# Balancer.net
KiCad netlist of a schematic drawn in Altium Designer
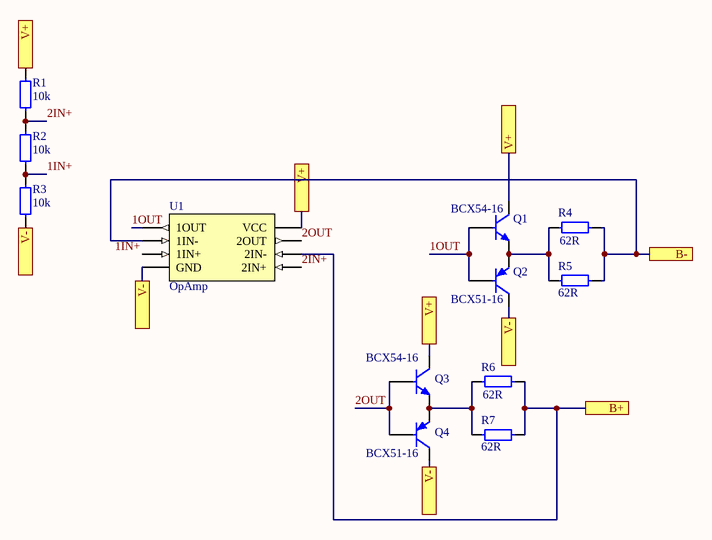
[diagram p0: Balancer.SchDoc]

(export (version "E")
  (design (tool "Eeschema 10.0.6"))
  (components
    (comp (ref "Q1")
      (value "BCX54-16")
      (footprint "SOT-89")
      (description "NPN general-purpose transistors")
      (fields (field (name "PART NUMBER") "BC817-40,215") (field (name "MANUFACTURER") "Nexperia"))
      (libsource (lib "BRT_Components") (part "NPN [BC817]"))
    )
    (comp (ref "Q2")
      (value "BCX51-16")
      (footprint "SOT-89")
      (description "PNP general-purpose transistors")
      (fields (field (name "PART NUMBER") "BC807,215") (field (name "MANUFACTURER") "Nexperia"))
      (libsource (lib "BRT_Components") (part "PNP [BC807]"))
    )
    (comp (ref "Q3")
      (value "BCX54-16")
      (footprint "SOT-89")
      (description "NPN general-purpose transistors")
      (fields (field (name "PART NUMBER") "BC817-40,215") (field (name "MANUFACTURER") "Nexperia"))
      (libsource (lib "BRT_Components") (part "NPN [BC817]"))
    )
    (comp (ref "Q4")
      (value "BCX51-16")
      (footprint "SOT-89")
      (description "PNP general-purpose transistors")
      (fields (field (name "PART NUMBER") "BC807,215") (field (name "MANUFACTURER") "Nexperia"))
      (libsource (lib "BRT_Components") (part "PNP [BC807]"))
    )
    (comp (ref "R1")
      (value "10k")
      (footprint "0805 Resistor")
      (description "0.125W 0805 10k, 1%")
      (fields (field (name "PART NUMBER") "RC0805FR-0710KL") (field (name "MANUFACTURER") "Taiwan"))
      (libsource (lib "BRT_Components") (part "Res 10k (0805)"))
    )
    (comp (ref "R2")
      (value "10k")
      (footprint "0805 Resistor")
      (description "0.125W 0805 10k, 1%")
      (fields (field (name "PART NUMBER") "RC0805FR-0710KL") (field (name "MANUFACTURER") "Taiwan"))
      (libsource (lib "BRT_Components") (part "Res 10k (0805)"))
    )
    (comp (ref "R3")
      (value "10k")
      (footprint "0805 Resistor")
      (description "0.125W 0805 10k, 1%")
      (fields (field (name "PART NUMBER") "RC0805FR-0710KL") (field (name "MANUFACTURER") "Taiwan"))
      (libsource (lib "BRT_Components") (part "Res 10k (0805)"))
    )
    (comp (ref "R4")
      (value "62R")
      (footprint "2512 Resistor")
      (description "1W 2512 62R, 1%")
      (fields (field (name "PART NUMBER") "RC2512FR-0762RL") (field (name "MANUFACTURER") "Taiwan"))
      (libsource (lib "BRT_Components") (part "Res 62R (2512)"))
    )
    (comp (ref "R5")
      (value "62R")
      (footprint "2512 Resistor")
      (description "1W 2512 62R, 1%")
      (fields (field (name "PART NUMBER") "RC2512FR-0762RL") (field (name "MANUFACTURER") "Taiwan"))
      (libsource (lib "BRT_Components") (part "Res 62R (2512)"))
    )
    (comp (ref "R6")
      (value "62R")
      (footprint "2512 Resistor")
      (description "1W 2512 62R, 1%")
      (fields (field (name "PART NUMBER") "RC2512FR-0762RL") (field (name "MANUFACTURER") "Taiwan"))
      (libsource (lib "BRT_Components") (part "Res 62R (2512)"))
    )
    (comp (ref "R7")
      (value "62R")
      (footprint "2512 Resistor")
      (description "1W 2512 62R, 1%")
      (fields (field (name "PART NUMBER") "RC2512FR-0762RL") (field (name "MANUFACTURER") "Taiwan"))
      (libsource (lib "BRT_Components") (part "Res 62R (2512)"))
    )
    (comp (ref "U1")
      (value "OpAmp")
      (footprint "SOIC-8")
      (description "Low Voltage Operational Amplifiers")
      (fields (field (name "PART NUMBER") "LMV358IDR") (field (name "MANUFACTURER") "Texas Instruments"))
      (libsource (lib "BRT_Components") (part "OpAmp [LMV358]"))
    )
  )
  (nets
    (net (code "1") (name "/1IN+") (class "Default")
      (node (ref "R2") (pin "1") (pinfunction "1_1") (pintype "passive"))
      (node (ref "R3") (pin "2") (pinfunction "2_2") (pintype "passive"))
      (node (ref "U1") (pin "3") (pinfunction "1IN+_3") (pintype "input"))
    )
    (net (code "2") (name "/1OUT") (class "Default")
      (node (ref "Q1") (pin "1") (pinfunction "1_1") (pintype "passive"))
      (node (ref "Q2") (pin "1") (pinfunction "1_1") (pintype "passive"))
      (node (ref "U1") (pin "1") (pinfunction "1OUT_1") (pintype "output"))
    )
    (net (code "3") (name "/2IN+") (class "Default")
      (node (ref "R1") (pin "1") (pinfunction "1_1") (pintype "passive"))
      (node (ref "R2") (pin "2") (pinfunction "2_2") (pintype "passive"))
      (node (ref "U1") (pin "5") (pinfunction "2IN+_5") (pintype "input"))
    )
    (net (code "4") (name "/2OUT") (class "Default")
      (node (ref "Q3") (pin "1") (pinfunction "1_1") (pintype "passive"))
      (node (ref "Q4") (pin "1") (pinfunction "1_1") (pintype "passive"))
      (node (ref "U1") (pin "7") (pinfunction "2OUT_7") (pintype "output"))
    )
    (net (code "5") (name "/B+") (class "Default")
      (node (ref "R6") (pin "2") (pinfunction "2_2") (pintype "passive"))
      (node (ref "R7") (pin "2") (pinfunction "2_2") (pintype "passive"))
      (node (ref "U1") (pin "6") (pinfunction "2IN-_6") (pintype "input"))
    )
    (net (code "6") (name "/B-") (class "Default")
      (node (ref "R4") (pin "2") (pinfunction "2_2") (pintype "passive"))
      (node (ref "R5") (pin "2") (pinfunction "2_2") (pintype "passive"))
      (node (ref "U1") (pin "2") (pinfunction "1IN-_2") (pintype "input"))
    )
    (net (code "7") (name "/V+") (class "Default")
      (node (ref "Q1") (pin "3") (pinfunction "3_3") (pintype "passive"))
      (node (ref "Q3") (pin "3") (pinfunction "3_3") (pintype "passive"))
      (node (ref "R1") (pin "2") (pinfunction "2_2") (pintype "passive"))
      (node (ref "U1") (pin "8") (pinfunction "VCC_8") (pintype "power_in"))
    )
    (net (code "8") (name "/V-") (class "Default")
      (node (ref "Q2") (pin "3") (pinfunction "3_3") (pintype "passive"))
      (node (ref "Q4") (pin "3") (pinfunction "3_3") (pintype "passive"))
      (node (ref "R3") (pin "1") (pinfunction "1_1") (pintype "passive"))
      (node (ref "U1") (pin "4") (pinfunction "GND_4") (pintype "power_in"))
    )
    (net (code "9") (name "Net-(Q1-Pad2)") (class "Default")
      (node (ref "Q1") (pin "2") (pinfunction "2_2") (pintype "passive"))
      (node (ref "Q2") (pin "2") (pinfunction "2_2") (pintype "passive"))
      (node (ref "R4") (pin "1") (pinfunction "1_1") (pintype "passive"))
      (node (ref "R5") (pin "1") (pinfunction "1_1") (pintype "passive"))
    )
    (net (code "10") (name "Net-(Q3-Pad2)") (class "Default")
      (node (ref "Q3") (pin "2") (pinfunction "2_2") (pintype "passive"))
      (node (ref "Q4") (pin "2") (pinfunction "2_2") (pintype "passive"))
      (node (ref "R6") (pin "1") (pinfunction "1_1") (pintype "passive"))
      (node (ref "R7") (pin "1") (pinfunction "1_1") (pintype "passive"))
    )
  )
)
